# INTERRUPTOR.net
KiCad netlist of a schematic drawn in EAGLE
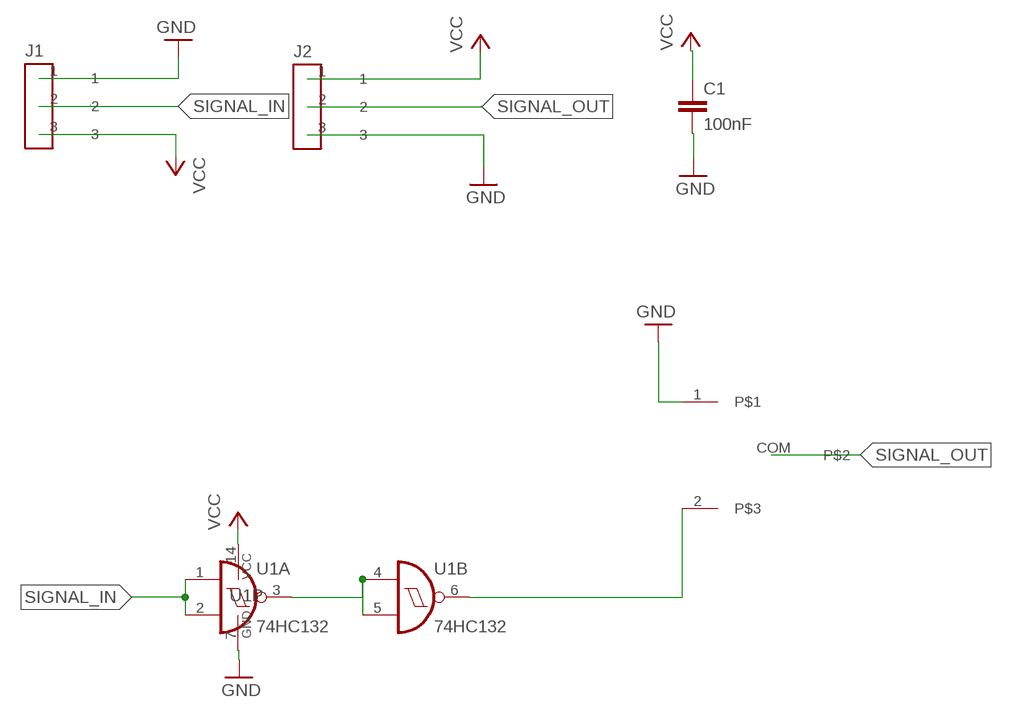
[diagram p0: schematic, sheet 1]

(export (version "E")
  (design (tool "Eeschema 10.0.6"))
  (components
    (comp (ref "C1")
      (value "100nF")
      (footprint "eagle-import:C0805")
      (libsource (lib "eagle-import") (part "C-EUC0805"))
    )
    (comp (ref "J1")
      (value "CONECTOR_MACHO")
      (footprint "eagle-import:3CONECTOR")
      (libsource (lib "eagle-import") (part "CONECTOR_MACHO"))
    )
    (comp (ref "J2")
      (value "CONECTOR_FEMEA")
      (footprint "eagle-import:3CONECTOR")
      (libsource (lib "eagle-import") (part "CONECTOR_FEMEA"))
    )
    (comp (ref "J3")
      (value "SS12F46")
      (footprint "eagle-import:SS12F46")
      (libsource (lib "eagle-import") (part "SS12F46"))
    )
    (comp (ref "U1")
      (value "74HC132")
      (footprint "eagle-import:SO14")
      (libsource (lib "eagle-import") (part "74132DHC"))
    )
  )
  (nets
    (net (code "1") (name "GND") (class "Default")
      (node (ref "C1") (pin "2") (pinfunction "2_2") (pintype "passive"))
      (node (ref "J1") (pin "1") (pinfunction "1_1") (pintype "bidirectional"))
      (node (ref "J2") (pin "3") (pinfunction "3_3") (pintype "bidirectional"))
      (node (ref "J3") (pin "1") (pinfunction "P$1_1") (pintype "bidirectional"))
      (node (ref "U1") (pin "7") (pinfunction "GND_7") (pintype "power_in"))
    )
    (net (code "2") (name "Net-(J3-P$3)") (class "Default")
      (node (ref "J3") (pin "2") (pinfunction "P$3_2") (pintype "bidirectional"))
      (node (ref "U1") (pin "6") (pinfunction "O_6") (pintype "output"))
    )
    (net (code "3") (name "Net-(U1A-O)") (class "Default")
      (node (ref "U1") (pin "3") (pinfunction "O_3") (pintype "output"))
      (node (ref "U1") (pin "4") (pinfunction "I0_4") (pintype "input"))
      (node (ref "U1") (pin "5") (pinfunction "I1_5") (pintype "input"))
    )
    (net (code "4") (name "SIGNAL_IN") (class "Default")
      (node (ref "J1") (pin "2") (pinfunction "2_2") (pintype "bidirectional"))
      (node (ref "U1") (pin "1") (pinfunction "I0_1") (pintype "input"))
      (node (ref "U1") (pin "2") (pinfunction "I1_2") (pintype "input"))
    )
    (net (code "5") (name "SIGNAL_OUT") (class "Default")
      (node (ref "J2") (pin "2") (pinfunction "2_2") (pintype "bidirectional"))
      (node (ref "J3") (pin "COM") (pinfunction "P$2_COM") (pintype "bidirectional"))
    )
    (net (code "6") (name "VCC") (class "Default")
      (node (ref "C1") (pin "1") (pinfunction "1_1") (pintype "passive"))
      (node (ref "J1") (pin "3") (pinfunction "3_3") (pintype "bidirectional"))
      (node (ref "J2") (pin "1") (pinfunction "1_1") (pintype "bidirectional"))
      (node (ref "U1") (pin "14") (pinfunction "VCC_14") (pintype "power_in"))
    )
  )
)
